# supply.net
KiCad netlist of a schematic drawn in Altium Designer
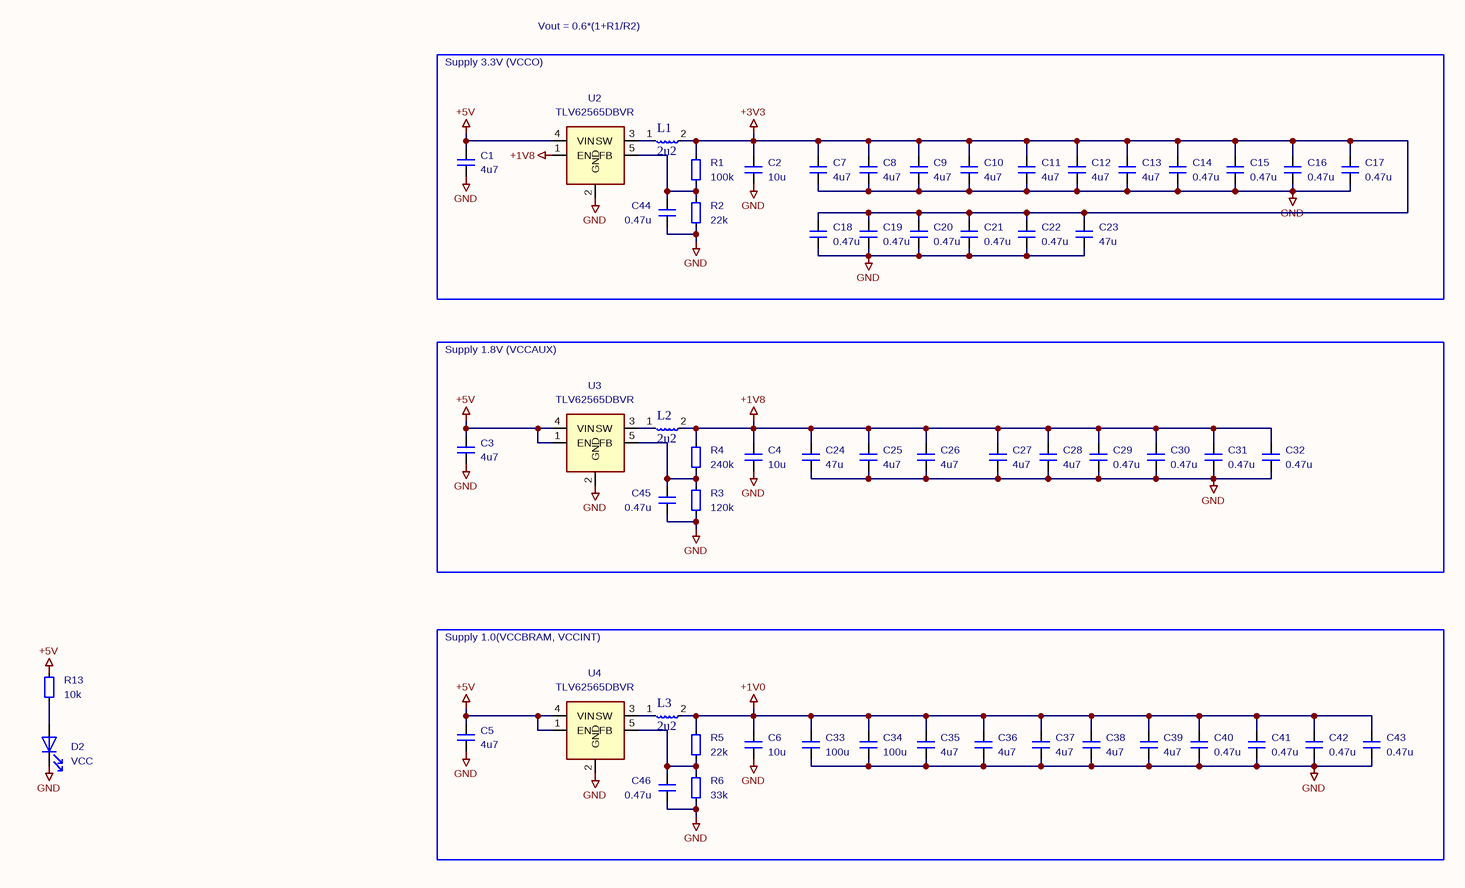
[diagram p0: supply.SchDoc]

(export (version "E")
  (design (tool "Eeschema 10.0.6"))
  (components
    (comp (ref "C1")
      (value "4u7")
      (footprint "C_0805_2012Metric")
      (libsource (lib "Device") (part "C_Small"))
    )
    (comp (ref "C2")
      (value "10u")
      (footprint "C_0805_2012Metric")
      (libsource (lib "Device") (part "C_Small"))
    )
    (comp (ref "C3")
      (value "4u7")
      (footprint "C_0805_2012Metric")
      (libsource (lib "Device") (part "C_Small"))
    )
    (comp (ref "C4")
      (value "10u")
      (footprint "C_0805_2012Metric")
      (libsource (lib "Device") (part "C_Small"))
    )
    (comp (ref "C5")
      (value "4u7")
      (footprint "C_0805_2012Metric")
      (libsource (lib "Device") (part "C_Small"))
    )
    (comp (ref "C6")
      (value "10u")
      (footprint "C_0805_2012Metric")
      (libsource (lib "Device") (part "C_Small"))
    )
    (comp (ref "C7")
      (value "4u7")
      (footprint "C_0805_2012Metric")
      (libsource (lib "Device") (part "C_Small"))
    )
    (comp (ref "C8")
      (value "4u7")
      (footprint "C_0805_2012Metric")
      (libsource (lib "Device") (part "C_Small"))
    )
    (comp (ref "C9")
      (value "4u7")
      (footprint "C_0805_2012Metric")
      (libsource (lib "Device") (part "C_Small"))
    )
    (comp (ref "C10")
      (value "4u7")
      (footprint "C_0805_2012Metric")
      (libsource (lib "Device") (part "C_Small"))
    )
    (comp (ref "C11")
      (value "4u7")
      (footprint "C_0805_2012Metric")
      (libsource (lib "Device") (part "C_Small"))
    )
    (comp (ref "C12")
      (value "4u7")
      (footprint "C_0805_2012Metric")
      (libsource (lib "Device") (part "C_Small"))
    )
    (comp (ref "C13")
      (value "4u7")
      (footprint "C_0805_2012Metric")
      (libsource (lib "Device") (part "C_Small"))
    )
    (comp (ref "C14")
      (value "0.47u")
      (footprint "C_0402_1005Metric")
      (libsource (lib "Device") (part "C_Small"))
    )
    (comp (ref "C15")
      (value "0.47u")
      (footprint "C_0402_1005Metric")
      (libsource (lib "Device") (part "C_Small"))
    )
    (comp (ref "C16")
      (value "0.47u")
      (footprint "C_0402_1005Metric")
      (libsource (lib "Device") (part "C_Small"))
    )
    (comp (ref "C17")
      (value "0.47u")
      (footprint "C_0402_1005Metric")
      (libsource (lib "Device") (part "C_Small"))
    )
    (comp (ref "C18")
      (value "0.47u")
      (footprint "C_0402_1005Metric")
      (libsource (lib "Device") (part "C_Small"))
    )
    (comp (ref "C19")
      (value "0.47u")
      (footprint "C_0402_1005Metric")
      (libsource (lib "Device") (part "C_Small"))
    )
    (comp (ref "C20")
      (value "0.47u")
      (footprint "C_0402_1005Metric")
      (libsource (lib "Device") (part "C_Small"))
    )
    (comp (ref "C21")
      (value "0.47u")
      (footprint "C_0402_1005Metric")
      (libsource (lib "Device") (part "C_Small"))
    )
    (comp (ref "C22")
      (value "0.47u")
      (footprint "C_0402_1005Metric")
      (libsource (lib "Device") (part "C_Small"))
    )
    (comp (ref "C23")
      (value "47u")
      (footprint "C_1206_3216Metric")
      (libsource (lib "Device") (part "C_Small"))
    )
    (comp (ref "C24")
      (value "47u")
      (footprint "C_1206_3216Metric")
      (libsource (lib "Device") (part "C_Small"))
    )
    (comp (ref "C25")
      (value "4u7")
      (footprint "C_0805_2012Metric")
      (libsource (lib "Device") (part "C_Small"))
    )
    (comp (ref "C26")
      (value "4u7")
      (footprint "C_0805_2012Metric")
      (libsource (lib "Device") (part "C_Small"))
    )
    (comp (ref "C27")
      (value "4u7")
      (footprint "C_0805_2012Metric")
      (libsource (lib "Device") (part "C_Small"))
    )
    (comp (ref "C28")
      (value "4u7")
      (footprint "C_0805_2012Metric")
      (libsource (lib "Device") (part "C_Small"))
    )
    (comp (ref "C29")
      (value "0.47u")
      (footprint "C_0402_1005Metric")
      (libsource (lib "Device") (part "C_Small"))
    )
    (comp (ref "C30")
      (value "0.47u")
      (footprint "C_0402_1005Metric")
      (libsource (lib "Device") (part "C_Small"))
    )
    (comp (ref "C31")
      (value "0.47u")
      (footprint "C_0402_1005Metric")
      (libsource (lib "Device") (part "C_Small"))
    )
    (comp (ref "C32")
      (value "0.47u")
      (footprint "C_0402_1005Metric")
      (libsource (lib "Device") (part "C_Small"))
    )
    (comp (ref "C33")
      (value "100u")
      (footprint "C_1206_3216Metric")
      (libsource (lib "Device") (part "C_Small"))
    )
    (comp (ref "C34")
      (value "100u")
      (footprint "C_1206_3216Metric")
      (libsource (lib "Device") (part "C_Small"))
    )
    (comp (ref "C35")
      (value "4u7")
      (footprint "C_0805_2012Metric")
      (libsource (lib "Device") (part "C_Small"))
    )
    (comp (ref "C36")
      (value "4u7")
      (footprint "C_0805_2012Metric")
      (libsource (lib "Device") (part "C_Small"))
    )
    (comp (ref "C37")
      (value "4u7")
      (footprint "C_0805_2012Metric")
      (libsource (lib "Device") (part "C_Small"))
    )
    (comp (ref "C38")
      (value "4u7")
      (footprint "C_0805_2012Metric")
      (libsource (lib "Device") (part "C_Small"))
    )
    (comp (ref "C39")
      (value "4u7")
      (footprint "C_0805_2012Metric")
      (libsource (lib "Device") (part "C_Small"))
    )
    (comp (ref "C40")
      (value "0.47u")
      (footprint "C_0402_1005Metric")
      (libsource (lib "Device") (part "C_Small"))
    )
    (comp (ref "C41")
      (value "0.47u")
      (footprint "C_0402_1005Metric")
      (libsource (lib "Device") (part "C_Small"))
    )
    (comp (ref "C42")
      (value "0.47u")
      (footprint "C_0402_1005Metric")
      (libsource (lib "Device") (part "C_Small"))
    )
    (comp (ref "C43")
      (value "0.47u")
      (footprint "C_0402_1005Metric")
      (libsource (lib "Device") (part "C_Small"))
    )
    (comp (ref "C44")
      (value "0.47u")
      (footprint "C_0402_1005Metric")
      (libsource (lib "Device") (part "C_Small"))
    )
    (comp (ref "C45")
      (value "0.47u")
      (footprint "C_0402_1005Metric")
      (libsource (lib "Device") (part "C_Small"))
    )
    (comp (ref "C46")
      (value "0.47u")
      (footprint "C_0402_1005Metric")
      (libsource (lib "Device") (part "C_Small"))
    )
    (comp (ref "D2") (value "VCC") (footprint "LED_0603_1608Metric") (libsource (lib "Device") (part "LED")))
    (comp (ref "L1")
      (value "2u2")
      (footprint "IND_LQH3NPN2R2MJRL")
      (libsource (lib "som_fpga") (part "L_Small"))
    )
    (comp (ref "L2")
      (value "2u2")
      (footprint "IND_LQH3NPN2R2MJRL")
      (libsource (lib "som_fpga") (part "L_Small"))
    )
    (comp (ref "L3")
      (value "2u2")
      (footprint "IND_LQH3NPN2R2MJRL")
      (libsource (lib "som_fpga") (part "L_Small"))
    )
    (comp (ref "R1")
      (value "100k")
      (footprint "R_0402_1005Metric")
      (libsource (lib "Device") (part "R_Small"))
    )
    (comp (ref "R2")
      (value "22k")
      (footprint "R_0402_1005Metric")
      (libsource (lib "Device") (part "R_Small"))
    )
    (comp (ref "R3")
      (value "120k")
      (footprint "R_0402_1005Metric")
      (libsource (lib "Device") (part "R_Small"))
    )
    (comp (ref "R4")
      (value "240k")
      (footprint "R_0402_1005Metric")
      (libsource (lib "Device") (part "R_Small"))
    )
    (comp (ref "R5")
      (value "22k")
      (footprint "R_0402_1005Metric")
      (libsource (lib "Device") (part "R_Small"))
    )
    (comp (ref "R6")
      (value "33k")
      (footprint "R_0402_1005Metric")
      (libsource (lib "Device") (part "R_Small"))
    )
    (comp (ref "R13")
      (value "10k")
      (footprint "R_0402_1005Metric")
      (libsource (lib "Device") (part "R_Small"))
    )
    (comp (ref "U2")
      (value "TLV62565DBVR")
      (footprint "SOT-23-5")
      (libsource (lib "Regulator_Switching") (part "NCP1529A"))
    )
    (comp (ref "U3")
      (value "TLV62565DBVR")
      (footprint "SOT-23-5")
      (libsource (lib "Regulator_Switching") (part "NCP1529A"))
    )
    (comp (ref "U4")
      (value "TLV62565DBVR")
      (footprint "SOT-23-5")
      (libsource (lib "Regulator_Switching") (part "NCP1529A"))
    )
  )
  (nets
    (net (code "1") (name "+1V0") (class "Default")
      (node (ref "C33") (pin "1") (pinfunction "1_1") (pintype "passive"))
      (node (ref "C34") (pin "1") (pinfunction "1_1") (pintype "passive"))
      (node (ref "C35") (pin "1") (pinfunction "1_1") (pintype "passive"))
      (node (ref "C36") (pin "1") (pinfunction "1_1") (pintype "passive"))
      (node (ref "C37") (pin "1") (pinfunction "1_1") (pintype "passive"))
      (node (ref "C38") (pin "1") (pinfunction "1_1") (pintype "passive"))
      (node (ref "C39") (pin "1") (pinfunction "1_1") (pintype "passive"))
      (node (ref "C40") (pin "1") (pinfunction "1_1") (pintype "passive"))
      (node (ref "C41") (pin "1") (pinfunction "1_1") (pintype "passive"))
      (node (ref "C42") (pin "1") (pinfunction "1_1") (pintype "passive"))
      (node (ref "C43") (pin "1") (pinfunction "1_1") (pintype "passive"))
      (node (ref "C6") (pin "1") (pinfunction "1_1") (pintype "passive"))
      (node (ref "L3") (pin "2") (pinfunction "2_2") (pintype "passive"))
      (node (ref "R5") (pin "1") (pinfunction "1_1") (pintype "passive"))
    )
    (net (code "2") (name "+1V8") (class "Default")
      (node (ref "C24") (pin "1") (pinfunction "1_1") (pintype "passive"))
      (node (ref "C25") (pin "1") (pinfunction "1_1") (pintype "passive"))
      (node (ref "C26") (pin "1") (pinfunction "1_1") (pintype "passive"))
      (node (ref "C27") (pin "1") (pinfunction "1_1") (pintype "passive"))
      (node (ref "C28") (pin "1") (pinfunction "1_1") (pintype "passive"))
      (node (ref "C29") (pin "1") (pinfunction "1_1") (pintype "passive"))
      (node (ref "C30") (pin "1") (pinfunction "1_1") (pintype "passive"))
      (node (ref "C31") (pin "1") (pinfunction "1_1") (pintype "passive"))
      (node (ref "C32") (pin "1") (pinfunction "1_1") (pintype "passive"))
      (node (ref "C4") (pin "1") (pinfunction "1_1") (pintype "passive"))
      (node (ref "L2") (pin "2") (pinfunction "2_2") (pintype "passive"))
      (node (ref "R4") (pin "1") (pinfunction "1_1") (pintype "passive"))
      (node (ref "U2") (pin "1") (pinfunction "EN_1") (pintype "passive"))
    )
    (net (code "3") (name "+3V3") (class "Default")
      (node (ref "C10") (pin "1") (pinfunction "1_1") (pintype "passive"))
      (node (ref "C11") (pin "1") (pinfunction "1_1") (pintype "passive"))
      (node (ref "C12") (pin "1") (pinfunction "1_1") (pintype "passive"))
      (node (ref "C13") (pin "1") (pinfunction "1_1") (pintype "passive"))
      (node (ref "C14") (pin "1") (pinfunction "1_1") (pintype "passive"))
      (node (ref "C15") (pin "1") (pinfunction "1_1") (pintype "passive"))
      (node (ref "C16") (pin "1") (pinfunction "1_1") (pintype "passive"))
      (node (ref "C17") (pin "1") (pinfunction "1_1") (pintype "passive"))
      (node (ref "C18") (pin "1") (pinfunction "1_1") (pintype "passive"))
      (node (ref "C19") (pin "1") (pinfunction "1_1") (pintype "passive"))
      (node (ref "C2") (pin "1") (pinfunction "1_1") (pintype "passive"))
      (node (ref "C20") (pin "1") (pinfunction "1_1") (pintype "passive"))
      (node (ref "C21") (pin "1") (pinfunction "1_1") (pintype "passive"))
      (node (ref "C22") (pin "1") (pinfunction "1_1") (pintype "passive"))
      (node (ref "C23") (pin "1") (pinfunction "1_1") (pintype "passive"))
      (node (ref "C7") (pin "1") (pinfunction "1_1") (pintype "passive"))
      (node (ref "C8") (pin "1") (pinfunction "1_1") (pintype "passive"))
      (node (ref "C9") (pin "1") (pinfunction "1_1") (pintype "passive"))
      (node (ref "L1") (pin "2") (pinfunction "2_2") (pintype "passive"))
      (node (ref "R1") (pin "1") (pinfunction "1_1") (pintype "passive"))
    )
    (net (code "4") (name "+5V") (class "Default")
      (node (ref "C1") (pin "1") (pinfunction "1_1") (pintype "passive"))
      (node (ref "C3") (pin "1") (pinfunction "1_1") (pintype "passive"))
      (node (ref "C5") (pin "1") (pinfunction "1_1") (pintype "passive"))
      (node (ref "R13") (pin "1") (pinfunction "1_1") (pintype "passive"))
      (node (ref "U2") (pin "4") (pinfunction "VIN_4") (pintype "passive"))
      (node (ref "U3") (pin "1") (pinfunction "EN_1") (pintype "passive"))
      (node (ref "U3") (pin "4") (pinfunction "VIN_4") (pintype "passive"))
      (node (ref "U4") (pin "1") (pinfunction "EN_1") (pintype "passive"))
      (node (ref "U4") (pin "4") (pinfunction "VIN_4") (pintype "passive"))
    )
    (net (code "5") (name "GND") (class "Default")
      (node (ref "C1") (pin "2") (pinfunction "2_2") (pintype "passive"))
      (node (ref "C10") (pin "2") (pinfunction "2_2") (pintype "passive"))
      (node (ref "C11") (pin "2") (pinfunction "2_2") (pintype "passive"))
      (node (ref "C12") (pin "2") (pinfunction "2_2") (pintype "passive"))
      (node (ref "C13") (pin "2") (pinfunction "2_2") (pintype "passive"))
      (node (ref "C14") (pin "2") (pinfunction "2_2") (pintype "passive"))
      (node (ref "C15") (pin "2") (pinfunction "2_2") (pintype "passive"))
      (node (ref "C16") (pin "2") (pinfunction "2_2") (pintype "passive"))
      (node (ref "C17") (pin "2") (pinfunction "2_2") (pintype "passive"))
      (node (ref "C18") (pin "2") (pinfunction "2_2") (pintype "passive"))
      (node (ref "C19") (pin "2") (pinfunction "2_2") (pintype "passive"))
      (node (ref "C2") (pin "2") (pinfunction "2_2") (pintype "passive"))
      (node (ref "C20") (pin "2") (pinfunction "2_2") (pintype "passive"))
      (node (ref "C21") (pin "2") (pinfunction "2_2") (pintype "passive"))
      (node (ref "C22") (pin "2") (pinfunction "2_2") (pintype "passive"))
      (node (ref "C23") (pin "2") (pinfunction "2_2") (pintype "passive"))
      (node (ref "C24") (pin "2") (pinfunction "2_2") (pintype "passive"))
      (node (ref "C25") (pin "2") (pinfunction "2_2") (pintype "passive"))
      (node (ref "C26") (pin "2") (pinfunction "2_2") (pintype "passive"))
      (node (ref "C27") (pin "2") (pinfunction "2_2") (pintype "passive"))
      (node (ref "C28") (pin "2") (pinfunction "2_2") (pintype "passive"))
      (node (ref "C29") (pin "2") (pinfunction "2_2") (pintype "passive"))
      (node (ref "C3") (pin "2") (pinfunction "2_2") (pintype "passive"))
      (node (ref "C30") (pin "2") (pinfunction "2_2") (pintype "passive"))
      (node (ref "C31") (pin "2") (pinfunction "2_2") (pintype "passive"))
      (node (ref "C32") (pin "2") (pinfunction "2_2") (pintype "passive"))
      (node (ref "C33") (pin "2") (pinfunction "2_2") (pintype "passive"))
      (node (ref "C34") (pin "2") (pinfunction "2_2") (pintype "passive"))
      (node (ref "C35") (pin "2") (pinfunction "2_2") (pintype "passive"))
      (node (ref "C36") (pin "2") (pinfunction "2_2") (pintype "passive"))
      (node (ref "C37") (pin "2") (pinfunction "2_2") (pintype "passive"))
      (node (ref "C38") (pin "2") (pinfunction "2_2") (pintype "passive"))
      (node (ref "C39") (pin "2") (pinfunction "2_2") (pintype "passive"))
      (node (ref "C4") (pin "2") (pinfunction "2_2") (pintype "passive"))
      (node (ref "C40") (pin "2") (pinfunction "2_2") (pintype "passive"))
      (node (ref "C41") (pin "2") (pinfunction "2_2") (pintype "passive"))
      (node (ref "C42") (pin "2") (pinfunction "2_2") (pintype "passive"))
      (node (ref "C43") (pin "2") (pinfunction "2_2") (pintype "passive"))
      (node (ref "C44") (pin "2") (pinfunction "2_2") (pintype "passive"))
      (node (ref "C45") (pin "2") (pinfunction "2_2") (pintype "passive"))
      (node (ref "C46") (pin "2") (pinfunction "2_2") (pintype "passive"))
      (node (ref "C5") (pin "2") (pinfunction "2_2") (pintype "passive"))
      (node (ref "C6") (pin "2") (pinfunction "2_2") (pintype "passive"))
      (node (ref "C7") (pin "2") (pinfunction "2_2") (pintype "passive"))
      (node (ref "C8") (pin "2") (pinfunction "2_2") (pintype "passive"))
      (node (ref "C9") (pin "2") (pinfunction "2_2") (pintype "passive"))
      (node (ref "D2") (pin "1") (pinfunction "K_1") (pintype "passive"))
      (node (ref "R2") (pin "2") (pinfunction "2_2") (pintype "passive"))
      (node (ref "R3") (pin "2") (pinfunction "2_2") (pintype "passive"))
      (node (ref "R6") (pin "2") (pinfunction "2_2") (pintype "passive"))
      (node (ref "U2") (pin "2") (pinfunction "GND_2") (pintype "passive"))
      (node (ref "U3") (pin "2") (pinfunction "GND_2") (pintype "passive"))
      (node (ref "U4") (pin "2") (pinfunction "GND_2") (pintype "passive"))
    )
    (net (code "6") (name "Net-(D2-A)") (class "Default")
      (node (ref "D2") (pin "2") (pinfunction "A_2") (pintype "passive"))
      (node (ref "R13") (pin "2") (pinfunction "2_2") (pintype "passive"))
    )
    (net (code "7") (name "Net-(U2-FB)") (class "Default")
      (node (ref "C44") (pin "1") (pinfunction "1_1") (pintype "passive"))
      (node (ref "R1") (pin "2") (pinfunction "2_2") (pintype "passive"))
      (node (ref "R2") (pin "1") (pinfunction "1_1") (pintype "passive"))
      (node (ref "U2") (pin "5") (pinfunction "FB_5") (pintype "passive"))
    )
    (net (code "8") (name "Net-(U2-SW)") (class "Default")
      (node (ref "L1") (pin "1") (pinfunction "1_1") (pintype "passive"))
      (node (ref "U2") (pin "3") (pinfunction "SW_3") (pintype "passive"))
    )
    (net (code "9") (name "Net-(U3-FB)") (class "Default")
      (node (ref "C45") (pin "1") (pinfunction "1_1") (pintype "passive"))
      (node (ref "R3") (pin "1") (pinfunction "1_1") (pintype "passive"))
      (node (ref "R4") (pin "2") (pinfunction "2_2") (pintype "passive"))
      (node (ref "U3") (pin "5") (pinfunction "FB_5") (pintype "passive"))
    )
    (net (code "10") (name "Net-(U3-SW)") (class "Default")
      (node (ref "L2") (pin "1") (pinfunction "1_1") (pintype "passive"))
      (node (ref "U3") (pin "3") (pinfunction "SW_3") (pintype "passive"))
    )
    (net (code "11") (name "Net-(U4-FB)") (class "Default")
      (node (ref "C46") (pin "1") (pinfunction "1_1") (pintype "passive"))
      (node (ref "R5") (pin "2") (pinfunction "2_2") (pintype "passive"))
      (node (ref "R6") (pin "1") (pinfunction "1_1") (pintype "passive"))
      (node (ref "U4") (pin "5") (pinfunction "FB_5") (pintype "passive"))
    )
    (net (code "12") (name "Net-(U4-SW)") (class "Default")
      (node (ref "L3") (pin "1") (pinfunction "1_1") (pintype "passive"))
      (node (ref "U4") (pin "3") (pinfunction "SW_3") (pintype "passive"))
    )
  )
)
